# PS3_PMIC.net
KiCad netlist of a schematic drawn in Altium Designer
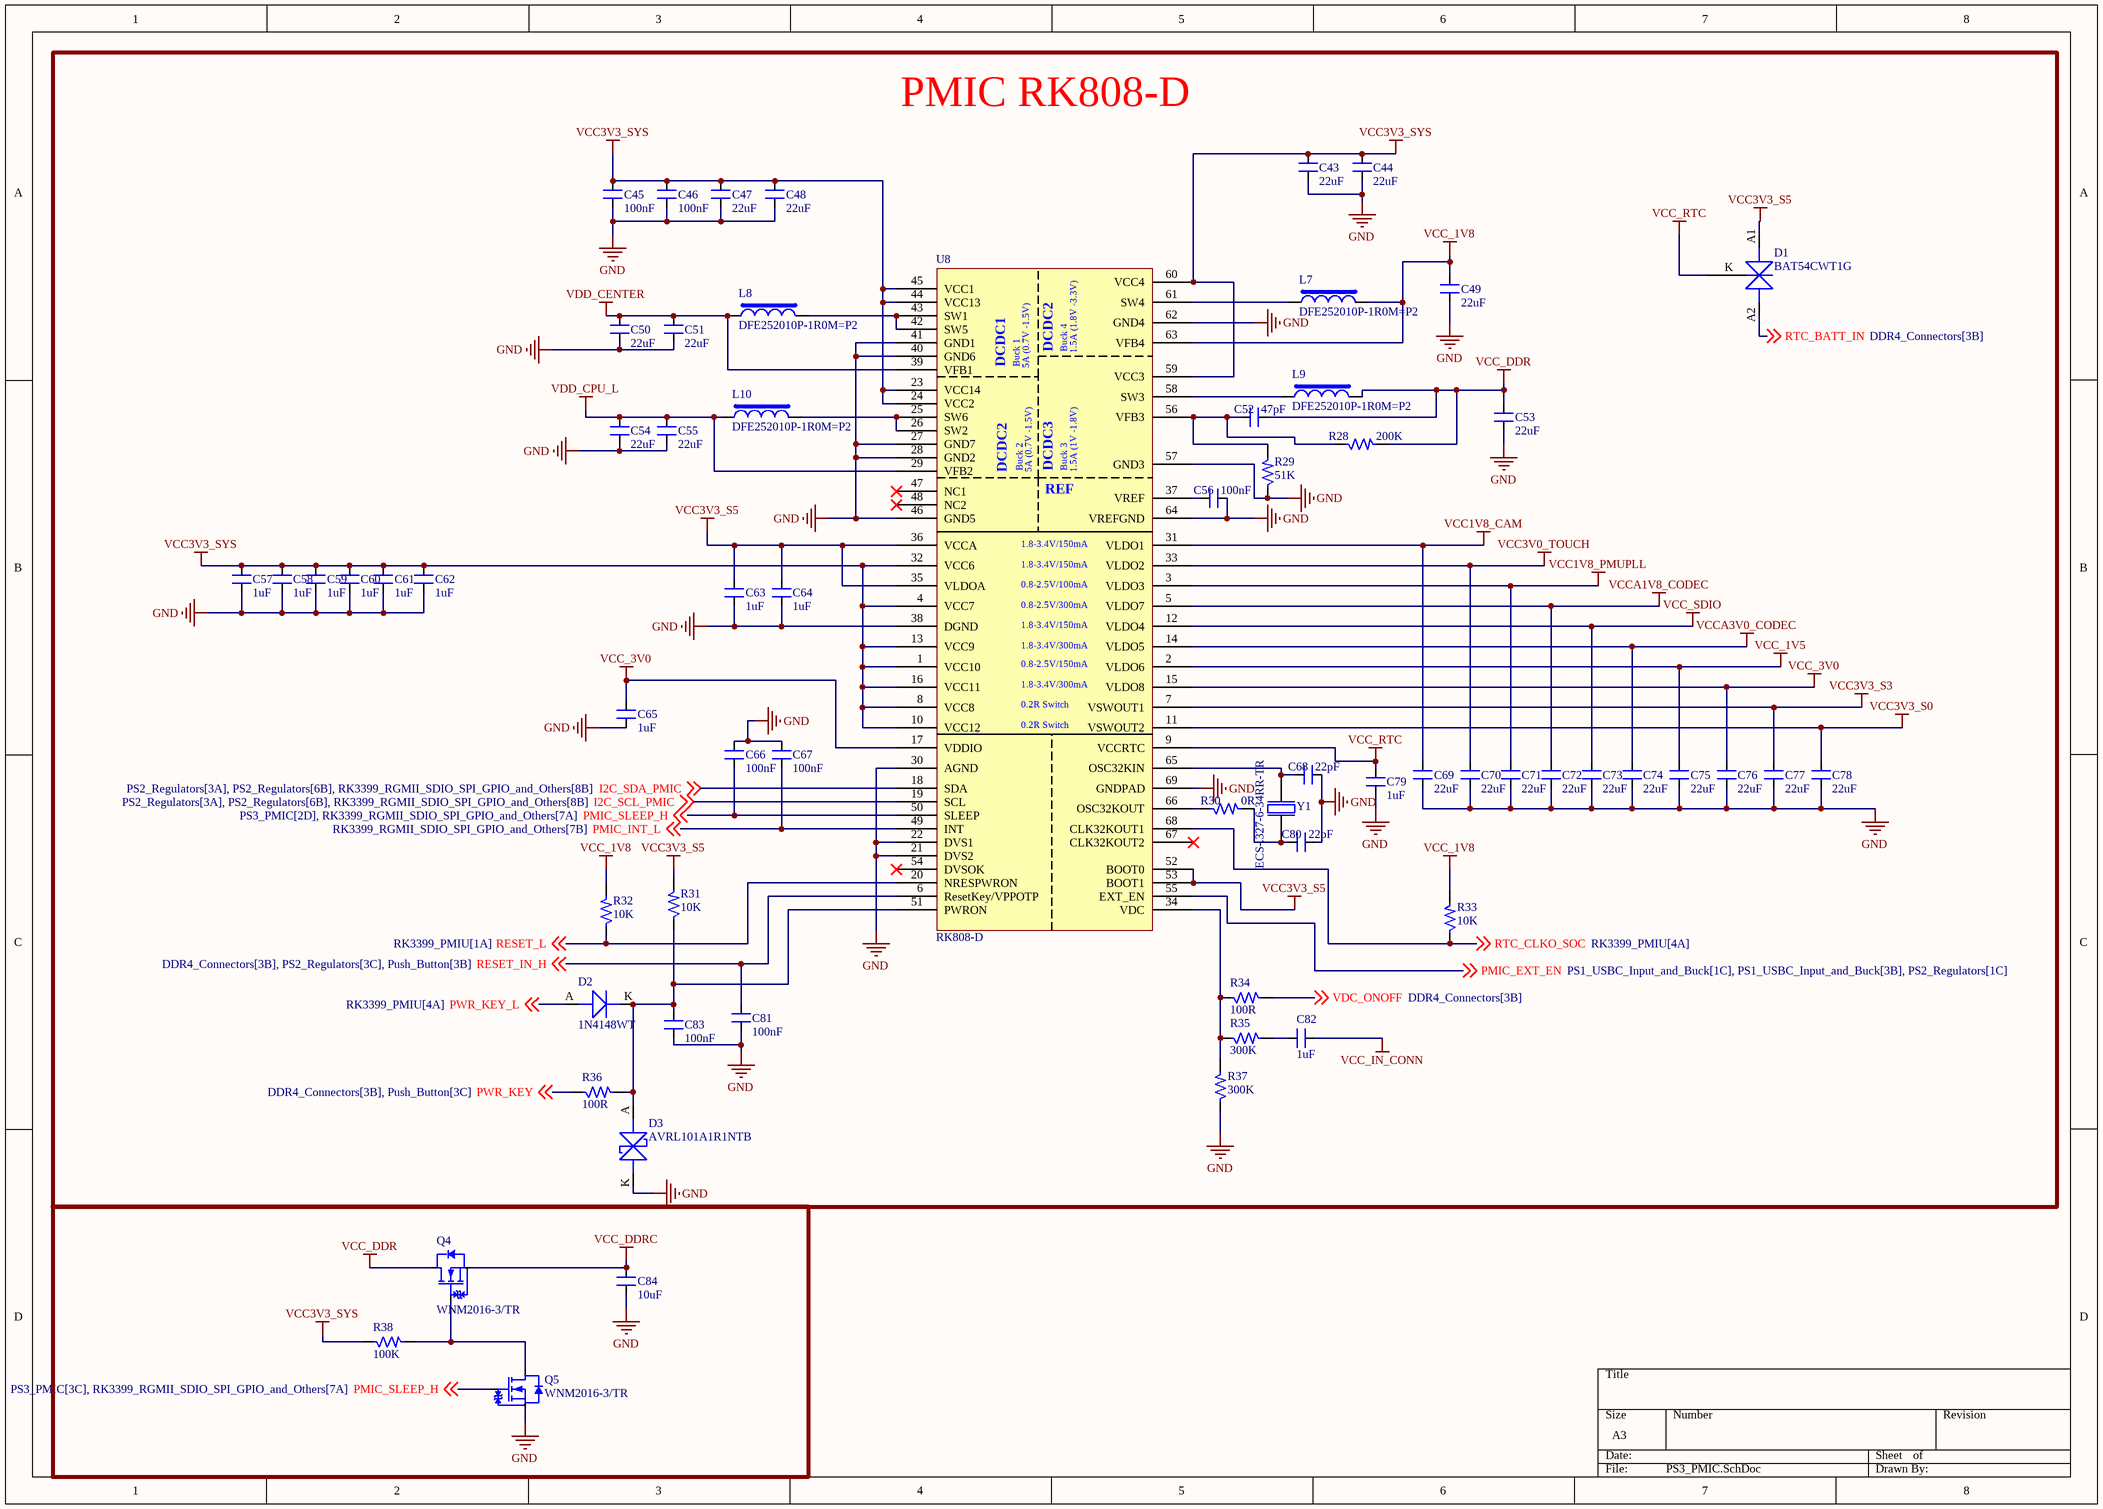
[diagram p0: PS3_PMIC.SchDoc]

(export (version "E")
  (design (tool "Eeschema 10.0.6"))
  (components
    (comp (ref "C43")
      (value "22uF")
      (footprint "CAP_0603")
      (description "22µF ±20% 10V Ceramic Capacitor X5R 0603 (1608 Metric)")
      (fields
        (field (name "MANUFACTURER") "Murata Electronics")
        (field (name "MANUFACTURER PART NUMBER") "GRM188R61A226ME15D")
      )
      (libsource (lib "EsteemPCB_SOM_Course_schlib") (part "CAP_22uF-10V-20%-0603"))
    )
    (comp (ref "C44")
      (value "22uF")
      (footprint "CAP_0603")
      (description "22µF ±20% 10V Ceramic Capacitor X5R 0603 (1608 Metric)")
      (fields
        (field (name "MANUFACTURER") "Murata Electronics")
        (field (name "MANUFACTURER PART NUMBER") "GRM188R61A226ME15D")
      )
      (libsource (lib "EsteemPCB_SOM_Course_schlib") (part "CAP_22uF-10V-20%-0603"))
    )
    (comp (ref "C45")
      (value "100nF")
      (footprint "CAP_0402")
      (description "0.1µF ±10% 25V Ceramic Capacitor X7R 0402 (1005 Metric)")
      (fields
        (field (name "MANUFACTURER") "Walsin Technology Corporation")
        (field (name "MANUFACTURER PART NUMBER") "0402B104K250CT")
      )
      (libsource (lib "EsteemPCB_SOM_Course_schlib") (part "CAP_100nF-25V-10%-0402"))
    )
    (comp (ref "C46")
      (value "100nF")
      (footprint "CAP_0402")
      (description "0.1µF ±10% 25V Ceramic Capacitor X7R 0402 (1005 Metric)")
      (fields
        (field (name "MANUFACTURER") "Walsin Technology Corporation")
        (field (name "MANUFACTURER PART NUMBER") "0402B104K250CT")
      )
      (libsource (lib "EsteemPCB_SOM_Course_schlib") (part "CAP_100nF-25V-10%-0402"))
    )
    (comp (ref "C47")
      (value "22uF")
      (footprint "CAP_0603")
      (description "22µF ±20% 10V Ceramic Capacitor X5R 0603 (1608 Metric)")
      (fields
        (field (name "MANUFACTURER") "Murata Electronics")
        (field (name "MANUFACTURER PART NUMBER") "GRM188R61A226ME15D")
      )
      (libsource (lib "EsteemPCB_SOM_Course_schlib") (part "CAP_22uF-10V-20%-0603"))
    )
    (comp (ref "C48")
      (value "22uF")
      (footprint "CAP_0603")
      (description "22µF ±20% 10V Ceramic Capacitor X5R 0603 (1608 Metric)")
      (fields
        (field (name "MANUFACTURER") "Murata Electronics")
        (field (name "MANUFACTURER PART NUMBER") "GRM188R61A226ME15D")
      )
      (libsource (lib "EsteemPCB_SOM_Course_schlib") (part "CAP_22uF-10V-20%-0603"))
    )
    (comp (ref "C49")
      (value "22uF")
      (footprint "CAP_0603")
      (description "22µF ±20% 10V Ceramic Capacitor X5R 0603 (1608 Metric)")
      (fields
        (field (name "MANUFACTURER") "Murata Electronics")
        (field (name "MANUFACTURER PART NUMBER") "GRM188R61A226ME15D")
      )
      (libsource (lib "EsteemPCB_SOM_Course_schlib") (part "CAP_22uF-10V-20%-0603"))
    )
    (comp (ref "C50")
      (value "22uF")
      (footprint "CAP_0603")
      (description "22µF ±20% 10V Ceramic Capacitor X5R 0603 (1608 Metric)")
      (fields
        (field (name "MANUFACTURER") "Murata Electronics")
        (field (name "MANUFACTURER PART NUMBER") "GRM188R61A226ME15D")
      )
      (libsource (lib "EsteemPCB_SOM_Course_schlib") (part "CAP_22uF-10V-20%-0603"))
    )
    (comp (ref "C51")
      (value "22uF")
      (footprint "CAP_0603")
      (description "22µF ±20% 10V Ceramic Capacitor X5R 0603 (1608 Metric)")
      (fields
        (field (name "MANUFACTURER") "Murata Electronics")
        (field (name "MANUFACTURER PART NUMBER") "GRM188R61A226ME15D")
      )
      (libsource (lib "EsteemPCB_SOM_Course_schlib") (part "CAP_22uF-10V-20%-0603"))
    )
    (comp (ref "C52")
      (value "47pF")
      (footprint "CAP_0402")
      (description "47pF ±10% 10V Ceramic Capacitor C0G, NP0 0402 (1005 Metric)")
      (fields
        (field (name "MANUFACTURER") "KEMET")
        (field (name "MANUFACTURER PART NUMBER") "C0402C470K8GAC7867")
      )
      (libsource (lib "EsteemPCB_SOM_Course_schlib") (part "CAP_47pF-10V-10%-0402"))
    )
    (comp (ref "C53")
      (value "22uF")
      (footprint "CAP_0603")
      (description "22µF ±20% 10V Ceramic Capacitor X5R 0603 (1608 Metric)")
      (fields
        (field (name "MANUFACTURER") "Murata Electronics")
        (field (name "MANUFACTURER PART NUMBER") "GRM188R61A226ME15D")
      )
      (libsource (lib "EsteemPCB_SOM_Course_schlib") (part "CAP_22uF-10V-20%-0603"))
    )
    (comp (ref "C54")
      (value "22uF")
      (footprint "CAP_0603")
      (description "22µF ±20% 10V Ceramic Capacitor X5R 0603 (1608 Metric)")
      (fields
        (field (name "MANUFACTURER") "Murata Electronics")
        (field (name "MANUFACTURER PART NUMBER") "GRM188R61A226ME15D")
      )
      (libsource (lib "EsteemPCB_SOM_Course_schlib") (part "CAP_22uF-10V-20%-0603"))
    )
    (comp (ref "C55")
      (value "22uF")
      (footprint "CAP_0603")
      (description "22µF ±20% 10V Ceramic Capacitor X5R 0603 (1608 Metric)")
      (fields
        (field (name "MANUFACTURER") "Murata Electronics")
        (field (name "MANUFACTURER PART NUMBER") "GRM188R61A226ME15D")
      )
      (libsource (lib "EsteemPCB_SOM_Course_schlib") (part "CAP_22uF-10V-20%-0603"))
    )
    (comp (ref "C56")
      (value "100nF")
      (footprint "CAP_0402")
      (description "0.1µF ±10% 25V Ceramic Capacitor X7R 0402 (1005 Metric)")
      (fields
        (field (name "MANUFACTURER") "Walsin Technology Corporation")
        (field (name "MANUFACTURER PART NUMBER") "0402B104K250CT")
      )
      (libsource (lib "EsteemPCB_SOM_Course_schlib") (part "CAP_100nF-25V-10%-0402"))
    )
    (comp (ref "C57")
      (value "1uF")
      (footprint "CAP_0402")
      (description "1µF ±10% 16V Ceramic Capacitor X5R 0402 (1005 Metric)")
      (fields
        (field (name "MANUFACTURER") "Knowles Novacap")
        (field (name "MANUFACTURER PART NUMBER") "0402BW105K160YT")
      )
      (libsource (lib "EsteemPCB_SOM_Course_schlib") (part "CAP_1uF-16V-10%-0402"))
    )
    (comp (ref "C58")
      (value "1uF")
      (footprint "CAP_0402")
      (description "1µF ±10% 16V Ceramic Capacitor X5R 0402 (1005 Metric)")
      (fields
        (field (name "MANUFACTURER") "Knowles Novacap")
        (field (name "MANUFACTURER PART NUMBER") "0402BW105K160YT")
      )
      (libsource (lib "EsteemPCB_SOM_Course_schlib") (part "CAP_1uF-16V-10%-0402"))
    )
    (comp (ref "C59")
      (value "1uF")
      (footprint "CAP_0402")
      (description "1µF ±10% 16V Ceramic Capacitor X5R 0402 (1005 Metric)")
      (fields
        (field (name "MANUFACTURER") "Knowles Novacap")
        (field (name "MANUFACTURER PART NUMBER") "0402BW105K160YT")
      )
      (libsource (lib "EsteemPCB_SOM_Course_schlib") (part "CAP_1uF-16V-10%-0402"))
    )
    (comp (ref "C60")
      (value "1uF")
      (footprint "CAP_0402")
      (description "1µF ±10% 16V Ceramic Capacitor X5R 0402 (1005 Metric)")
      (fields
        (field (name "MANUFACTURER") "Knowles Novacap")
        (field (name "MANUFACTURER PART NUMBER") "0402BW105K160YT")
      )
      (libsource (lib "EsteemPCB_SOM_Course_schlib") (part "CAP_1uF-16V-10%-0402"))
    )
    (comp (ref "C61")
      (value "1uF")
      (footprint "CAP_0402")
      (description "1µF ±10% 16V Ceramic Capacitor X5R 0402 (1005 Metric)")
      (fields
        (field (name "MANUFACTURER") "Knowles Novacap")
        (field (name "MANUFACTURER PART NUMBER") "0402BW105K160YT")
      )
      (libsource (lib "EsteemPCB_SOM_Course_schlib") (part "CAP_1uF-16V-10%-0402"))
    )
    (comp (ref "C62")
      (value "1uF")
      (footprint "CAP_0402")
      (description "1µF ±10% 16V Ceramic Capacitor X5R 0402 (1005 Metric)")
      (fields
        (field (name "MANUFACTURER") "Knowles Novacap")
        (field (name "MANUFACTURER PART NUMBER") "0402BW105K160YT")
      )
      (libsource (lib "EsteemPCB_SOM_Course_schlib") (part "CAP_1uF-16V-10%-0402"))
    )
    (comp (ref "C63")
      (value "1uF")
      (footprint "CAP_0402")
      (description "1µF ±10% 16V Ceramic Capacitor X5R 0402 (1005 Metric)")
      (fields
        (field (name "MANUFACTURER") "Knowles Novacap")
        (field (name "MANUFACTURER PART NUMBER") "0402BW105K160YT")
      )
      (libsource (lib "EsteemPCB_SOM_Course_schlib") (part "CAP_1uF-16V-10%-0402"))
    )
    (comp (ref "C64")
      (value "1uF")
      (footprint "CAP_0402")
      (description "1µF ±10% 16V Ceramic Capacitor X5R 0402 (1005 Metric)")
      (fields
        (field (name "MANUFACTURER") "Knowles Novacap")
        (field (name "MANUFACTURER PART NUMBER") "0402BW105K160YT")
      )
      (libsource (lib "EsteemPCB_SOM_Course_schlib") (part "CAP_1uF-16V-10%-0402"))
    )
    (comp (ref "C65")
      (value "1uF")
      (footprint "CAP_0402")
      (description "1µF ±10% 16V Ceramic Capacitor X5R 0402 (1005 Metric)")
      (fields
        (field (name "MANUFACTURER") "Knowles Novacap")
        (field (name "MANUFACTURER PART NUMBER") "0402BW105K160YT")
      )
      (libsource (lib "EsteemPCB_SOM_Course_schlib") (part "CAP_1uF-16V-10%-0402"))
    )
    (comp (ref "C66")
      (value "100nF")
      (footprint "CAP_0402")
      (description "0.1µF ±10% 25V Ceramic Capacitor X7R 0402 (1005 Metric)")
      (fields
        (field (name "MANUFACTURER") "Walsin Technology Corporation")
        (field (name "MANUFACTURER PART NUMBER") "0402B104K250CT")
      )
      (libsource (lib "EsteemPCB_SOM_Course_schlib") (part "CAP_100nF-25V-10%-0402"))
    )
    (comp (ref "C67")
      (value "100nF")
      (footprint "CAP_0402")
      (description "0.1µF ±10% 25V Ceramic Capacitor X7R 0402 (1005 Metric)")
      (fields
        (field (name "MANUFACTURER") "Walsin Technology Corporation")
        (field (name "MANUFACTURER PART NUMBER") "0402B104K250CT")
      )
      (libsource (lib "EsteemPCB_SOM_Course_schlib") (part "CAP_100nF-25V-10%-0402"))
    )
    (comp (ref "C68")
      (value "22pF")
      (footprint "CAP_0402")
      (description "22pF ±10% 10V Ceramic Capacitor C0G, NP0 0402 (1005 Metric)")
      (fields
        (field (name "MANUFACTURER") "KEMET")
        (field (name "MANUFACTURER PART NUMBER") "C0402C220K8GACTU")
      )
      (libsource (lib "EsteemPCB_SOM_Course_schlib") (part "CAP_22pF-10V-10%-0402"))
    )
    (comp (ref "C69")
      (value "22uF")
      (footprint "CAP_0603")
      (description "22µF ±20% 10V Ceramic Capacitor X5R 0603 (1608 Metric)")
      (fields
        (field (name "MANUFACTURER") "Murata Electronics")
        (field (name "MANUFACTURER PART NUMBER") "GRM188R61A226ME15D")
      )
      (libsource (lib "EsteemPCB_SOM_Course_schlib") (part "CAP_22uF-10V-20%-0603"))
    )
    (comp (ref "C70")
      (value "22uF")
      (footprint "CAP_0603")
      (description "22µF ±20% 10V Ceramic Capacitor X5R 0603 (1608 Metric)")
      (fields
        (field (name "MANUFACTURER") "Murata Electronics")
        (field (name "MANUFACTURER PART NUMBER") "GRM188R61A226ME15D")
      )
      (libsource (lib "EsteemPCB_SOM_Course_schlib") (part "CAP_22uF-10V-20%-0603"))
    )
    (comp (ref "C71")
      (value "22uF")
      (footprint "CAP_0603")
      (description "22µF ±20% 10V Ceramic Capacitor X5R 0603 (1608 Metric)")
      (fields
        (field (name "MANUFACTURER") "Murata Electronics")
        (field (name "MANUFACTURER PART NUMBER") "GRM188R61A226ME15D")
      )
      (libsource (lib "EsteemPCB_SOM_Course_schlib") (part "CAP_22uF-10V-20%-0603"))
    )
    (comp (ref "C72")
      (value "22uF")
      (footprint "CAP_0603")
      (description "22µF ±20% 10V Ceramic Capacitor X5R 0603 (1608 Metric)")
      (fields
        (field (name "MANUFACTURER") "Murata Electronics")
        (field (name "MANUFACTURER PART NUMBER") "GRM188R61A226ME15D")
      )
      (libsource (lib "EsteemPCB_SOM_Course_schlib") (part "CAP_22uF-10V-20%-0603"))
    )
    (comp (ref "C73")
      (value "22uF")
      (footprint "CAP_0603")
      (description "22µF ±20% 10V Ceramic Capacitor X5R 0603 (1608 Metric)")
      (fields
        (field (name "MANUFACTURER") "Murata Electronics")
        (field (name "MANUFACTURER PART NUMBER") "GRM188R61A226ME15D")
      )
      (libsource (lib "EsteemPCB_SOM_Course_schlib") (part "CAP_22uF-10V-20%-0603"))
    )
    (comp (ref "C74")
      (value "22uF")
      (footprint "CAP_0603")
      (description "22µF ±20% 10V Ceramic Capacitor X5R 0603 (1608 Metric)")
      (fields
        (field (name "MANUFACTURER") "Murata Electronics")
        (field (name "MANUFACTURER PART NUMBER") "GRM188R61A226ME15D")
      )
      (libsource (lib "EsteemPCB_SOM_Course_schlib") (part "CAP_22uF-10V-20%-0603"))
    )
    (comp (ref "C75")
      (value "22uF")
      (footprint "CAP_0603")
      (description "22µF ±20% 10V Ceramic Capacitor X5R 0603 (1608 Metric)")
      (fields
        (field (name "MANUFACTURER") "Murata Electronics")
        (field (name "MANUFACTURER PART NUMBER") "GRM188R61A226ME15D")
      )
      (libsource (lib "EsteemPCB_SOM_Course_schlib") (part "CAP_22uF-10V-20%-0603"))
    )
    (comp (ref "C76")
      (value "22uF")
      (footprint "CAP_0603")
      (description "22µF ±20% 10V Ceramic Capacitor X5R 0603 (1608 Metric)")
      (fields
        (field (name "MANUFACTURER") "Murata Electronics")
        (field (name "MANUFACTURER PART NUMBER") "GRM188R61A226ME15D")
      )
      (libsource (lib "EsteemPCB_SOM_Course_schlib") (part "CAP_22uF-10V-20%-0603"))
    )
    (comp (ref "C77")
      (value "22uF")
      (footprint "CAP_0603")
      (description "22µF ±20% 10V Ceramic Capacitor X5R 0603 (1608 Metric)")
      (fields
        (field (name "MANUFACTURER") "Murata Electronics")
        (field (name "MANUFACTURER PART NUMBER") "GRM188R61A226ME15D")
      )
      (libsource (lib "EsteemPCB_SOM_Course_schlib") (part "CAP_22uF-10V-20%-0603"))
    )
    (comp (ref "C78")
      (value "22uF")
      (footprint "CAP_0603")
      (description "22µF ±20% 10V Ceramic Capacitor X5R 0603 (1608 Metric)")
      (fields
        (field (name "MANUFACTURER") "Murata Electronics")
        (field (name "MANUFACTURER PART NUMBER") "GRM188R61A226ME15D")
      )
      (libsource (lib "EsteemPCB_SOM_Course_schlib") (part "CAP_22uF-10V-20%-0603"))
    )
    (comp (ref "C79")
      (value "1uF")
      (footprint "CAP_0402")
      (description "1µF ±10% 16V Ceramic Capacitor X5R 0402 (1005 Metric)")
      (fields
        (field (name "MANUFACTURER") "Knowles Novacap")
        (field (name "MANUFACTURER PART NUMBER") "0402BW105K160YT")
      )
      (libsource (lib "EsteemPCB_SOM_Course_schlib") (part "CAP_1uF-16V-10%-0402"))
    )
    (comp (ref "C80")
      (value "22pF")
      (footprint "CAP_0402")
      (description "22pF ±10% 10V Ceramic Capacitor C0G, NP0 0402 (1005 Metric)")
      (fields
        (field (name "MANUFACTURER") "KEMET")
        (field (name "MANUFACTURER PART NUMBER") "C0402C220K8GACTU")
      )
      (libsource (lib "EsteemPCB_SOM_Course_schlib") (part "CAP_22pF-10V-10%-0402"))
    )
    (comp (ref "C81")
      (value "100nF")
      (footprint "CAP_0402")
      (description "0.1µF ±10% 25V Ceramic Capacitor X7R 0402 (1005 Metric)")
      (fields
        (field (name "MANUFACTURER") "Walsin Technology Corporation")
        (field (name "MANUFACTURER PART NUMBER") "0402B104K250CT")
      )
      (libsource (lib "EsteemPCB_SOM_Course_schlib") (part "CAP_100nF-25V-10%-0402"))
    )
    (comp (ref "C82")
      (value "1uF")
      (footprint "CAP_0402")
      (description "1µF ±10% 16V Ceramic Capacitor X5R 0402 (1005 Metric)")
      (fields
        (field (name "MANUFACTURER") "Knowles Novacap")
        (field (name "MANUFACTURER PART NUMBER") "0402BW105K160YT")
      )
      (libsource (lib "EsteemPCB_SOM_Course_schlib") (part "CAP_1uF-16V-10%-0402"))
    )
    (comp (ref "C83")
      (value "100nF")
      (footprint "CAP_0402")
      (description "0.1µF ±10% 25V Ceramic Capacitor X7R 0402 (1005 Metric)")
      (fields
        (field (name "MANUFACTURER") "Walsin Technology Corporation")
        (field (name "MANUFACTURER PART NUMBER") "0402B104K250CT")
      )
      (libsource (lib "EsteemPCB_SOM_Course_schlib") (part "CAP_100nF-25V-10%-0402"))
    )
    (comp (ref "C84")
      (value "10uF")
      (footprint "CAP_0402")
      (description "10µF ±20% 10V Ceramic Capacitor X5R 0402 (1005 Metric)")
      (fields
        (field (name "MANUFACTURER PART NUMBER") "CL05A106MP5NUNC")
        (field (name "MANUFACTURER") "Samsung Electro-Mechanics")
      )
      (libsource (lib "EsteemPCB_SOM_Course_schlib") (part "CAP_10uF-10V-20%-0402"))
    )
    (comp (ref "D1")
      (value "BAT54CWT1G")
      (footprint "DIO_SOT-323-3")
      (description "Diode Array 1 Pair Common Cathode Schottky 30V 200mA (DC) Surface Mount SC-70, SOT-323")
      (fields (field (name "MANUFACTURER") "ON Semiconductor"))
      (libsource (lib "EsteemPCB_SOM_Course_schlib") (part "DIO-S-A_30V-200mA-SOT-323"))
    )
    (comp (ref "D2")
      (value "1N4148WT")
      (footprint "DIO_SOD523")
      (description "Diode Standard 100V 300mA (DC) Surface Mount SOD-123")
      (fields (field (name "MANUFACTURER") "FAIRCHILD"))
      (libsource (lib "EsteemPCB_SOM_Course_schlib") (part "DIO_75V-200mA-SOD-523F"))
    )
    (comp (ref "D3")
      (value "AVRL101A1R1NTB")
      (footprint "DIO_0402_SMD")
      (description "39V Varistor 1 Circuit Surface Mount, MLCV 0402 (1005 Metric)")
      (fields (field (name "MANUFACTURER") "TDK Corporation"))
      (libsource (lib "EsteemPCB_SOM_Course_schlib") (part "DIO-T_10V-39V-0402"))
    )
    (comp (ref "L7")
      (value "DFE252010P-1R0M=P2")
      (footprint "IND_1008")
      (description "1µH Shielded Wirewound Inductor 3.8A 54mOhm Max 1008 (2520 Metric)")
      (fields (field (name "MANUFACTURER") "Murata Electronics"))
      (libsource (lib "EsteemPCB_SOM_Course_schlib") (part "IND_1uH-3.8A-20%-1008"))
    )
    (comp (ref "L8")
      (value "DFE252010P-1R0M=P2")
      (footprint "IND_1008")
      (description "1µH Shielded Wirewound Inductor 3.8A 54mOhm Max 1008 (2520 Metric)")
      (fields (field (name "MANUFACTURER") "Murata Electronics"))
      (libsource (lib "EsteemPCB_SOM_Course_schlib") (part "IND_1uH-3.8A-20%-1008"))
    )
    (comp (ref "L9")
      (value "DFE252010P-1R0M=P2")
      (footprint "IND_1008")
      (description "1µH Shielded Wirewound Inductor 3.8A 54mOhm Max 1008 (2520 Metric)")
      (fields (field (name "MANUFACTURER") "Murata Electronics"))
      (libsource (lib "EsteemPCB_SOM_Course_schlib") (part "IND_1uH-3.8A-20%-1008"))
    )
    (comp (ref "L10")
      (value "DFE252010P-1R0M=P2")
      (footprint "IND_1008")
      (description "1µH Shielded Wirewound Inductor 3.8A 54mOhm Max 1008 (2520 Metric)")
      (fields (field (name "MANUFACTURER") "Murata Electronics"))
      (libsource (lib "EsteemPCB_SOM_Course_schlib") (part "IND_1uH-3.8A-20%-1008"))
    )
    (comp (ref "Q4")
      (value "WNM2016-3/TR")
      (footprint "SOT 23-3")
      (description "N Channel 20V 2.9A 1V @ 250uA 47mΩ @ 3.6A,4.5V 700mW SOT-23(SOT-23-3) MOSFET RoHS")
      (fields (field (name "MANUFACTURER") "WILLSEMI(Will Semicon)"))
      (libsource (lib "EsteemPCB_SOM_Course_schlib") (part "MOSFET-N_20V-2.9A-SOT-23"))
    )
    (comp (ref "Q5")
      (value "WNM2016-3/TR")
      (footprint "SOT 23-3")
      (description "N Channel 20V 2.9A 1V @ 250uA 47mΩ @ 3.6A,4.5V 700mW SOT-23(SOT-23-3) MOSFET RoHS")
      (fields (field (name "MANUFACTURER") "WILLSEMI(Will Semicon)"))
      (libsource (lib "EsteemPCB_SOM_Course_schlib") (part "MOSFET-N_20V-2.9A-SOT-23"))
    )
    (comp (ref "R28")
      (value "200K")
      (footprint "RES_0402")
      (description "200 kOhms ±1% 0.1W, 1/10W Chip Resistor 0402 (1005 Metric) Automotive AEC-Q200 Thick Film")
      (fields
        (field (name "MANUFACTURER") "Panasonic Electronic Components")
        (field (name "MANUFACTURER PART NUMBER") "ERJ-2RKF2003X")
      )
      (libsource (lib "EsteemPCB_SOM_Course_schlib") (part "RES_200K-0.1W-1%-0402"))
    )
    (comp (ref "R29")
      (value "51K")
      (footprint "RES_0402")
      (description "51 kOhms ±1% 0.1W, 1/10W Chip Resistor 0402 (1005 Metric) Automotive AEC-Q200 Thick Film")
      (fields
        (field (name "MANUFACTURER") "Panasonic Electronic Components")
        (field (name "MANUFACTURER PART NUMBER") "ERJ-2RKF5102X")
      )
      (libsource (lib "EsteemPCB_SOM_Course_schlib") (part "RES_51K-0.1W-1%-0402"))
    )
    (comp (ref "R30")
      (value "0R")
      (footprint "RES_0402")
      (description "0 Ohms Jumper 0.1W, 1/10W Chip Resistor 0402 (1005 Metric) Automotive AEC-Q200 Thick Film")
      (fields
        (field (name "MANUFACTURER") "Panasonic Electronic Components")
        (field (name "MANUFACTURER PART NUMBER") "ERJ-2GE0R00X")
      )
      (libsource (lib "EsteemPCB_SOM_Course_schlib") (part "RES_0R-0.1W-1%-0402"))
    )
    (comp (ref "R31")
      (value "10K")
      (footprint "RES_0402")
      (description "10 kOhms ±1% 0.1W, 1/10W Chip Resistor 0402 (1005 Metric) Anti-Sulfur Thin Film")
      (fields
        (field (name "MANUFACTURER") "Vishay Beyschlag/Draloric/BC Components")
        (field (name "MANUFACTURER PART NUMBER") "MCS04020C1002FE000")
      )
      (libsource (lib "EsteemPCB_SOM_Course_schlib") (part "RES_10K-0.1W-1%-0402"))
    )
    (comp (ref "R32")
      (value "10K")
      (footprint "RES_0402")
      (description "10 kOhms ±1% 0.1W, 1/10W Chip Resistor 0402 (1005 Metric) Anti-Sulfur Thin Film")
      (fields
        (field (name "MANUFACTURER") "Vishay Beyschlag/Draloric/BC Components")
        (field (name "MANUFACTURER PART NUMBER") "MCS04020C1002FE000")
      )
      (libsource (lib "EsteemPCB_SOM_Course_schlib") (part "RES_10K-0.1W-1%-0402"))
    )
    (comp (ref "R33")
      (value "10K")
      (footprint "RES_0402")
      (description "10 kOhms ±1% 0.1W, 1/10W Chip Resistor 0402 (1005 Metric) Anti-Sulfur Thin Film")
      (fields
        (field (name "MANUFACTURER") "Vishay Beyschlag/Draloric/BC Components")
        (field (name "MANUFACTURER PART NUMBER") "MCS04020C1002FE000")
      )
      (libsource (lib "EsteemPCB_SOM_Course_schlib") (part "RES_10K-0.1W-1%-0402"))
    )
    (comp (ref "R34")
      (value "100R")
      (footprint "RES_0402")
      (fields
        (field (name "MANUFACTURER") "KOA Speer Electronics, Inc.")
        (field (name "MANUFACTURER PART NUMBER") "RK73H1ETTP1000F")
      )
      (libsource (lib "EsteemPCB_SOM_Course_schlib") (part "RES_100R-0.1W-1%-0402"))
    )
    (comp (ref "R35")
      (value "300K")
      (footprint "RES_0402")
      (description "300 kOhms ±1% 0.1W, 1/10W Chip Resistor 0402 (1005 Metric) Automotive AEC-Q200 Thick Film")
      (fields
        (field (name "MANUFACTURER") "Panasonic Electronic Components")
        (field (name "MANUFACTURER PART NUMBER") "ERJ-2RKF3003X")
      )
      (libsource (lib "EsteemPCB_SOM_Course_schlib") (part "RES_300K-0.1W-1%-0402"))
    )
    (comp (ref "R36")
      (value "100R")
      (footprint "RES_0402")
      (fields
        (field (name "MANUFACTURER") "KOA Speer Electronics, Inc.")
        (field (name "MANUFACTURER PART NUMBER") "RK73H1ETTP1000F")
      )
      (libsource (lib "EsteemPCB_SOM_Course_schlib") (part "RES_100R-0.1W-1%-0402"))
    )
    (comp (ref "R37")
      (value "300K")
      (footprint "RES_0402")
      (description "300 kOhms ±1% 0.1W, 1/10W Chip Resistor 0402 (1005 Metric) Automotive AEC-Q200 Thick Film")
      (fields
        (field (name "MANUFACTURER") "Panasonic Electronic Components")
        (field (name "MANUFACTURER PART NUMBER") "ERJ-2RKF3003X")
      )
      (libsource (lib "EsteemPCB_SOM_Course_schlib") (part "RES_300K-0.1W-1%-0402"))
    )
    (comp (ref "R38")
      (value "100K")
      (footprint "RES_0402")
      (description "100 kOhms ±1% 0.1W, 1/10W Chip Resistor 0402 (1005 Metric) Anti-Sulfur Thin Film")
      (fields
        (field (name "MANUFACTURER") "Vishay Beyschlag/Draloric/BC Components")
        (field (name "MANUFACTURER PART NUMBER") "MCS04020C1003FE000")
      )
      (libsource (lib "EsteemPCB_SOM_Course_schlib") (part "RES_100K-0.1W-1%-0402"))
    )
    (comp (ref "U8")
      (value "RK808-D")
      (footprint "QFN68_13.7_220.4X220.4_SMD")
      (description "The RK808 is a complete power supply solution for Portable systems.")
      (fields (field (name "MANUFACTURER") "Rockchip"))
      (libsource (lib "EsteemPCB_SOM_Course_schlib") (part "IC_RK808-D-QFN68"))
    )
    (comp (ref "Y1")
      (value "ECS-.327-6-34RR-TR")
      (footprint "XTAL_ECS-.327-6-34RR-TR")
      (description "32.768kHz ±20ppm Crystal 12pF 80 kOhms 2-SMD, No Lead")
      (fields (field (name "MANUFACTURER") "Ecliptek"))
      (libsource (lib "EsteemPCB_SOM_Course_schlib") (part "XTAL_32.768Khz-22pF-SMD"))
    )
  )
  (nets
    (net (code "1") (name "GND") (class "Default")
      (node (ref "C43") (pin "1") (pinfunction "1_1") (pintype "passive"))
      (node (ref "C44") (pin "1") (pinfunction "1_1") (pintype "passive"))
      (node (ref "C45") (pin "1") (pinfunction "1_1") (pintype "passive"))
      (node (ref "C46") (pin "1") (pinfunction "1_1") (pintype "passive"))
      (node (ref "C47") (pin "1") (pinfunction "1_1") (pintype "passive"))
      (node (ref "C48") (pin "1") (pinfunction "1_1") (pintype "passive"))
      (node (ref "C49") (pin "1") (pinfunction "1_1") (pintype "passive"))
      (node (ref "C50") (pin "1") (pinfunction "1_1") (pintype "passive"))
      (node (ref "C51") (pin "1") (pinfunction "1_1") (pintype "passive"))
      (node (ref "C53") (pin "1") (pinfunction "1_1") (pintype "passive"))
      (node (ref "C54") (pin "1") (pinfunction "1_1") (pintype "passive"))
      (node (ref "C55") (pin "1") (pinfunction "1_1") (pintype "passive"))
      (node (ref "C56") (pin "2") (pinfunction "2_2") (pintype "passive"))
      (node (ref "C57") (pin "1") (pinfunction "1_1") (pintype "passive"))
      (node (ref "C58") (pin "1") (pinfunction "1_1") (pintype "passive"))
      (node (ref "C59") (pin "1") (pinfunction "1_1") (pintype "passive"))
      (node (ref "C60") (pin "1") (pinfunction "1_1") (pintype "passive"))
      (node (ref "C61") (pin "1") (pinfunction "1_1") (pintype "passive"))
      (node (ref "C62") (pin "1") (pinfunction "1_1") (pintype "passive"))
      (node (ref "C63") (pin "1") (pinfunction "1_1") (pintype "passive"))
      (node (ref "C64") (pin "1") (pinfunction "1_1") (pintype "passive"))
      (node (ref "C65") (pin "1") (pinfunction "1_1") (pintype "passive"))
      (node (ref "C66") (pin "2") (pinfunction "2_2") (pintype "passive"))
      (node (ref "C67") (pin "2") (pinfunction "2_2") (pintype "passive"))
      (node (ref "C68") (pin "2") (pinfunction "2_2") (pintype "passive"))
      (node (ref "C69") (pin "1") (pinfunction "1_1") (pintype "passive"))
      (node (ref "C70") (pin "1") (pinfunction "1_1") (pintype "passive"))
      (node (ref "C71") (pin "1") (pinfunction "1_1") (pintype "passive"))
      (node (ref "C72") (pin "1") (pinfunction "1_1") (pintype "passive"))
      (node (ref "C73") (pin "1") (pinfunction "1_1") (pintype "passive"))
      (node (ref "C74") (pin "1") (pinfunction "1_1") (pintype "passive"))
      (node (ref "C75") (pin "1") (pinfunction "1_1") (pintype "passive"))
      (node (ref "C76") (pin "1") (pinfunction "1_1") (pintype "passive"))
      (node (ref "C77") (pin "1") (pinfunction "1_1") (pintype "passive"))
      (node (ref "C78") (pin "1") (pinfunction "1_1") (pintype "passive"))
      (node (ref "C79") (pin "1") (pinfunction "1_1") (pintype "passive"))
      (node (ref "C80") (pin "2") (pinfunction "2_2") (pintype "passive"))
      (node (ref "C81") (pin "1") (pinfunction "1_1") (pintype "passive"))
      (node (ref "C83") (pin "1") (pinfunction "1_1") (pintype "passive"))
      (node (ref "C84") (pin "1") (pinfunction "1_1") (pintype "passive"))
      (node (ref "D3") (pin "K") (pinfunction "K_K") (pintype "passive"))
      (node (ref "Q5") (pin "2") (pinfunction "S_2") (pintype "passive"))
      (node (ref "R29") (pin "1") (pinfunction "1_1") (pintype "passive"))
      (node (ref "R37") (pin "1") (pinfunction "1_1") (pintype "passive"))
      (node (ref "U8") (pin "21") (pinfunction "DVS2_21") (pintype "passive"))
      (node (ref "U8") (pin "22") (pinfunction "DVS1_22") (pintype "passive"))
      (node (ref "U8") (pin "27") (pinfunction "GND7_27") (pintype "passive"))
      (node (ref "U8") (pin "28") (pinfunction "GND2_28") (pintype "passive"))
      (node (ref "U8") (pin "30") (pinfunction "AGND_30") (pintype "passive"))
      (node (ref "U8") (pin "38") (pinfunction "DGND_38") (pintype "passive"))
      (node (ref "U8") (pin "40") (pinfunction "GND6_40") (pintype "passive"))
      (node (ref "U8") (pin "41") (pinfunction "GND1_41") (pintype "passive"))
      (node (ref "U8") (pin "46") (pinfunction "GND5_46") (pintype "passive"))
      (node (ref "U8") (pin "57") (pinfunction "GND3_57") (pintype "passive"))
      (node (ref "U8") (pin "62") (pinfunction "GND4_62") (pintype "passive"))
      (node (ref "U8") (pin "64") (pinfunction "VREFGND_64") (pintype "passive"))
      (node (ref "U8") (pin "69") (pinfunction "GNDPAD_69") (pintype "passive"))
    )
    (net (code "2") (name "I2C_SCL_PMIC") (class "Default")
      (node (ref "U8") (pin "19") (pinfunction "SCL_19") (pintype "passive"))
    )
    (net (code "3") (name "I2C_SDA_PMIC") (class "Default")
      (node (ref "U8") (pin "18") (pinfunction "SDA_18") (pintype "passive"))
    )
    (net (code "4") (name "Net-(C80-Pad1)") (class "Default")
      (node (ref "C80") (pin "1") (pinfunction "1_1") (pintype "passive"))
      (node (ref "R30") (pin "2") (pinfunction "2_2") (pintype "passive"))
      (node (ref "Y1") (pin "1") (pinfunction "1_1") (pintype "passive"))
    )
    (net (code "5") (name "Net-(C82-Pad1)") (class "Default")
      (node (ref "C82") (pin "1") (pinfunction "1_1") (pintype "passive"))
      (node (ref "R35") (pin "2") (pinfunction "2_2") (pintype "passive"))
    )
    (net (code "6") (name "Net-(D2-CATHODE)") (class "Default")
      (node (ref "C83") (pin "2") (pinfunction "2_2") (pintype "passive"))
      (node (ref "D2") (pin "K") (pinfunction "CATHODE_K") (pintype "passive"))
      (node (ref "D3") (pin "A") (pinfunction "A_A") (pintype "passive"))
      (node (ref "R31") (pin "1") (pinfunction "1_1") (pintype "passive"))
      (node (ref "R36") (pin "2") (pinfunction "2_2") (pintype "passive"))
      (node (ref "U8") (pin "51") (pinfunction "PWRON_51") (pintype "passive"))
    )
    (net (code "7") (name "Net-(Q4-G)") (class "Default")
      (node (ref "Q4") (pin "1") (pinfunction "G_1") (pintype "passive"))
      (node (ref "Q5") (pin "3") (pinfunction "D_3") (pintype "passive"))
      (node (ref "R38") (pin "2") (pinfunction "2_2") (pintype "passive"))
    )
    (net (code "8") (name "Net-(U8-OSC32KIN)") (class "Default")
      (node (ref "C68") (pin "1") (pinfunction "1_1") (pintype "passive"))
      (node (ref "U8") (pin "65") (pinfunction "OSC32KIN_65") (pintype "passive"))
      (node (ref "Y1") (pin "2") (pinfunction "2_2") (pintype "passive"))
    )
    (net (code "9") (name "Net-(U8-OSC32KOUT)") (class "Default")
      (node (ref "R30") (pin "1") (pinfunction "1_1") (pintype "passive"))
      (node (ref "U8") (pin "66") (pinfunction "OSC32KOUT_66") (pintype "passive"))
    )
    (net (code "10") (name "Net-(U8-SW1)") (class "Default")
      (node (ref "L8") (pin "2") (pinfunction "2_2") (pintype "passive"))
      (node (ref "U8") (pin "42") (pinfunction "SW5_42") (pintype "passive"))
      (node (ref "U8") (pin "43") (pinfunction "SW1_43") (pintype "passive"))
    )
    (net (code "11") (name "Net-(U8-SW2)") (class "Default")
      (node (ref "L10") (pin "2") (pinfunction "2_2") (pintype "passive"))
      (node (ref "U8") (pin "25") (pinfunction "SW6_25") (pintype "passive"))
      (node (ref "U8") (pin "26") (pinfunction "SW2_26") (pintype "passive"))
    )
    (net (code "12") (name "Net-(U8-SW3)") (class "Default")
      (node (ref "L9") (pin "1") (pinfunction "1_1") (pintype "passive"))
      (node (ref "U8") (pin "58") (pinfunction "SW3_58") (pintype "passive"))
    )
    (net (code "13") (name "Net-(U8-SW4)") (class "Default")
      (node (ref "L7") (pin "1") (pinfunction "1_1") (pintype "passive"))
      (node (ref "U8") (pin "61") (pinfunction "SW4_61") (pintype "passive"))
    )
    (net (code "14") (name "Net-(U8-VDC)") (class "Default")
      (node (ref "R34") (pin "1") (pinfunction "1_1") (pintype "passive"))
      (node (ref "R35") (pin "1") (pinfunction "1_1") (pintype "passive"))
      (node (ref "R37") (pin "2") (pinfunction "2_2") (pintype "passive"))
      (node (ref "U8") (pin "34") (pinfunction "VDC_34") (pintype "passive"))
    )
    (net (code "15") (name "Net-(U8-VFB3)") (class "Default")
      (node (ref "C52") (pin "1") (pinfunction "1_1") (pintype "passive"))
      (node (ref "R28") (pin "1") (pinfunction "1_1") (pintype "passive"))
      (node (ref "R29") (pin "2") (pinfunction "2_2") (pintype "passive"))
      (node (ref "U8") (pin "56") (pinfunction "VFB3_56") (pintype "passive"))
    )
    (net (code "16") (name "Net-(U8-VREF)") (class "Default")
      (node (ref "C56") (pin "1") (pinfunction "1_1") (pintype "passive"))
      (node (ref "U8") (pin "37") (pinfunction "VREF_37") (pintype "passive"))
    )
    (net (code "17") (name "PMIC_EXT_EN") (class "Default")
      (node (ref "U8") (pin "55") (pinfunction "EXT_EN_55") (pintype "passive"))
    )
    (net (code "18") (name "PMIC_INT_L") (class "Default")
      (node (ref "C67") (pin "1") (pinfunction "1_1") (pintype "passive"))
      (node (ref "U8") (pin "49") (pinfunction "INT_49") (pintype "passive"))
    )
    (net (code "19") (name "PMIC_SLEEP_H") (class "Default")
      (node (ref "C66") (pin "1") (pinfunction "1_1") (pintype "passive"))
      (node (ref "Q5") (pin "1") (pinfunction "G_1") (pintype "passive"))
      (node (ref "U8") (pin "50") (pinfunction "SLEEP_50") (pintype "passive"))
    )
    (net (code "20") (name "PWR_KEY") (class "Default")
      (node (ref "R36") (pin "1") (pinfunction "1_1") (pintype "passive"))
    )
    (net (code "21") (name "PWR_KEY_L") (class "Default")
      (node (ref "D2") (pin "A") (pinfunction "ANODE_A") (pintype "passive"))
    )
    (net (code "22") (name "RESET_IN_H") (class "Default")
      (node (ref "C81") (pin "2") (pinfunction "2_2") (pintype "passive"))
      (node (ref "U8") (pin "6") (pinfunction "ResetKey/VPPOTP_6") (pintype "passive"))
    )
    (net (code "23") (name "RESET_L") (class "Default")
      (node (ref "R32") (pin "1") (pinfunction "1_1") (pintype "passive"))
      (node (ref "U8") (pin "20") (pinfunction "NRESPWRON_20") (pintype "passive"))
    )
    (net (code "24") (name "RTC_BATT_IN") (class "Default")
      (node (ref "D1") (pin "A2") (pinfunction "A2_A2") (pintype "passive"))
    )
    (net (code "25") (name "RTC_CLKO_SOC") (class "Default")
      (node (ref "R33") (pin "1") (pinfunction "1_1") (pintype "passive"))
      (node (ref "U8") (pin "68") (pinfunction "CLK32KOUT1_68") (pintype "passive"))
    )
    (net (code "26") (name "VCC1V8_CAM") (class "Default")
      (node (ref "C69") (pin "2") (pinfunction "2_2") (pintype "passive"))
      (node (ref "U8") (pin "31") (pinfunction "VLDO1_31") (pintype "passive"))
    )
    (net (code "27") (name "VCC1V8_PMUPLL") (class "Default")
      (node (ref "C71") (pin "2") (pinfunction "2_2") (pintype "passive"))
      (node (ref "U8") (pin "3") (pinfunction "VLDO3_3") (pintype "passive"))
    )
    (net (code "28") (name "VCC3V0_TOUCH") (class "Default")
      (node (ref "C70") (pin "2") (pinfunction "2_2") (pintype "passive"))
      (node (ref "U8") (pin "33") (pinfunction "VLDO2_33") (pintype "passive"))
    )
    (net (code "29") (name "VCC3V3_S0") (class "Default")
      (node (ref "C78") (pin "2") (pinfunction "2_2") (pintype "passive"))
      (node (ref "U8") (pin "11") (pinfunction "VSWOUT2_11") (pintype "passive"))
    )
    (net (code "30") (name "VCC3V3_S3") (class "Default")
      (node (ref "C77") (pin "2") (pinfunction "2_2") (pintype "passive"))
      (node (ref "U8") (pin "7") (pinfunction "VSWOUT1_7") (pintype "passive"))
    )
    (net (code "31") (name "VCC3V3_S5") (class "Default")
      (node (ref "C63") (pin "2") (pinfunction "2_2") (pintype "passive"))
      (node (ref "C64") (pin "2") (pinfunction "2_2") (pintype "passive"))
      (node (ref "D1") (pin "A1") (pinfunction "A1_A1") (pintype "passive"))
      (node (ref "R31") (pin "2") (pinfunction "2_2") (pintype "passive"))
      (node (ref "U8") (pin "35") (pinfunction "VLDOA_35") (pintype "passive"))
      (node (ref "U8") (pin "36") (pinfunction "VCCA_36") (pintype "passive"))
      (node (ref "U8") (pin "52") (pinfunction "BOOT0_52") (pintype "passive"))
      (node (ref "U8") (pin "53") (pinfunction "BOOT1_53") (pintype "passive"))
    )
    (net (code "32") (name "VCC3V3_SYS") (class "Default")
      (node (ref "C43") (pin "2") (pinfunction "2_2") (pintype "passive"))
      (node (ref "C44") (pin "2") (pinfunction "2_2") (pintype "passive"))
      (node (ref "C45") (pin "2") (pinfunction "2_2") (pintype "passive"))
      (node (ref "C46") (pin "2") (pinfunction "2_2") (pintype "passive"))
      (node (ref "C47") (pin "2") (pinfunction "2_2") (pintype "passive"))
      (node (ref "C48") (pin "2") (pinfunction "2_2") (pintype "passive"))
      (node (ref "C57") (pin "2") (pinfunction "2_2") (pintype "passive"))
      (node (ref "C58") (pin "2") (pinfunction "2_2") (pintype "passive"))
      (node (ref "C59") (pin "2") (pinfunction "2_2") (pintype "passive"))
      (node (ref "C60") (pin "2") (pinfunction "2_2") (pintype "passive"))
      (node (ref "C61") (pin "2") (pinfunction "2_2") (pintype "passive"))
      (node (ref "C62") (pin "2") (pinfunction "2_2") (pintype "passive"))
      (node (ref "R38") (pin "1") (pinfunction "1_1") (pintype "passive"))
      (node (ref "U8") (pin "1") (pinfunction "VCC10_1") (pintype "passive"))
      (node (ref "U8") (pin "10") (pinfunction "VCC12_10") (pintype "passive"))
      (node (ref "U8") (pin "13") (pinfunction "VCC9_13") (pintype "passive"))
      (node (ref "U8") (pin "16") (pinfunction "VCC11_16") (pintype "passive"))
      (node (ref "U8") (pin "23") (pinfunction "VCC14_23") (pintype "passive"))
      (node (ref "U8") (pin "24") (pinfunction "VCC2_24") (pintype "passive"))
      (node (ref "U8") (pin "32") (pinfunction "VCC6_32") (pintype "passive"))
      (node (ref "U8") (pin "4") (pinfunction "VCC7_4") (pintype "passive"))
      (node (ref "U8") (pin "44") (pinfunction "VCC13_44") (pintype "passive"))
      (node (ref "U8") (pin "45") (pinfunction "VCC1_45") (pintype "passive"))
      (node (ref "U8") (pin "59") (pinfunction "VCC3_59") (pintype "passive"))
      (node (ref "U8") (pin "60") (pinfunction "VCC4_60") (pintype "passive"))
      (node (ref "U8") (pin "8") (pinfunction "VCC8_8") (pintype "passive"))
    )
    (net (code "33") (name "VCCA1V8_CODEC") (class "Default")
      (node (ref "C72") (pin "2") (pinfunction "2_2") (pintype "passive"))
      (node (ref "U8") (pin "5") (pinfunction "VLDO7_5") (pintype "passive"))
    )
    (net (code "34") (name "VCCA3V0_CODEC") (class "Default")
      (node (ref "C74") (pin "2") (pinfunction "2_2") (pintype "passive"))
      (node (ref "U8") (pin "14") (pinfunction "VLDO5_14") (pintype "passive"))
    )
    (net (code "35") (name "VCC_1V5") (class "Default")
      (node (ref "C75") (pin "2") (pinfunction "2_2") (pintype "passive"))
      (node (ref "U8") (pin "2") (pinfunction "VLDO6_2") (pintype "passive"))
    )
    (net (code "36") (name "VCC_1V8") (class "Default")
      (node (ref "C49") (pin "2") (pinfunction "2_2") (pintype "passive"))
      (node (ref "L7") (pin "2") (pinfunction "2_2") (pintype "passive"))
      (node (ref "R32") (pin "2") (pinfunction "2_2") (pintype "passive"))
      (node (ref "R33") (pin "2") (pinfunction "2_2") (pintype "passive"))
      (node (ref "U8") (pin "63") (pinfunction "VFB4_63") (pintype "passive"))
    )
    (net (code "37") (name "VCC_3V0") (class "Default")
      (node (ref "C65") (pin "2") (pinfunction "2_2") (pintype "passive"))
      (node (ref "C76") (pin "2") (pinfunction "2_2") (pintype "passive"))
      (node (ref "U8") (pin "15") (pinfunction "VLDO8_15") (pintype "passive"))
      (node (ref "U8") (pin "17") (pinfunction "VDDIO_17") (pintype "passive"))
    )
    (net (code "38") (name "VCC_DDR") (class "Default")
      (node (ref "C52") (pin "2") (pinfunction "2_2") (pintype "passive"))
      (node (ref "C53") (pin "2") (pinfunction "2_2") (pintype "passive"))
      (node (ref "L9") (pin "2") (pinfunction "2_2") (pintype "passive"))
      (node (ref "Q4") (pin "3") (pinfunction "D_3") (pintype "passive"))
      (node (ref "R28") (pin "2") (pinfunction "2_2") (pintype "passive"))
    )
    (net (code "39") (name "VCC_DDRC") (class "Default")
      (node (ref "C84") (pin "2") (pinfunction "2_2") (pintype "passive"))
      (node (ref "Q4") (pin "2") (pinfunction "S_2") (pintype "passive"))
    )
    (net (code "40") (name "VCC_IN_CONN") (class "Default")
      (node (ref "C82") (pin "2") (pinfunction "2_2") (pintype "passive"))
    )
    (net (code "41") (name "VCC_RTC") (class "Default")
      (node (ref "C79") (pin "2") (pinfunction "2_2") (pintype "passive"))
      (node (ref "D1") (pin "K") (pinfunction "K_K") (pintype "passive"))
      (node (ref "U8") (pin "9") (pinfunction "VCCRTC_9") (pintype "passive"))
    )
    (net (code "42") (name "VCC_SDIO") (class "Default")
      (node (ref "C73") (pin "2") (pinfunction "2_2") (pintype "passive"))
      (node (ref "U8") (pin "12") (pinfunction "VLDO4_12") (pintype "passive"))
    )
    (net (code "43") (name "VDC_ONOFF") (class "Default")
      (node (ref "R34") (pin "2") (pinfunction "2_2") (pintype "passive"))
    )
    (net (code "44") (name "VDD_CENTER") (class "Default")
      (node (ref "C50") (pin "2") (pinfunction "2_2") (pintype "passive"))
      (node (ref "C51") (pin "2") (pinfunction "2_2") (pintype "passive"))
      (node (ref "L8") (pin "1") (pinfunction "1_1") (pintype "passive"))
      (node (ref "U8") (pin "39") (pinfunction "VFB1_39") (pintype "passive"))
    )
    (net (code "45") (name "VDD_CPU_L") (class "Default")
      (node (ref "C54") (pin "2") (pinfunction "2_2") (pintype "passive"))
      (node (ref "C55") (pin "2") (pinfunction "2_2") (pintype "passive"))
      (node (ref "L10") (pin "1") (pinfunction "1_1") (pintype "passive"))
      (node (ref "U8") (pin "29") (pinfunction "VFB2_29") (pintype "passive"))
    )
    (net (code "46") (name "unconnected-(U8-CLK32KOUT2-Pad67)") (class "Default")
      (node (ref "U8") (pin "67") (pinfunction "CLK32KOUT2_67") (pintype "passive+no_connect"))
    )
    (net (code "47") (name "unconnected-(U8-DVSOK-Pad54)") (class "Default")
      (node (ref "U8") (pin "54") (pinfunction "DVSOK_54") (pintype "passive+no_connect"))
    )
    (net (code "48") (name "unconnected-(U8-NC1-Pad47)") (class "Default")
      (node (ref "U8") (pin "47") (pinfunction "NC1_47") (pintype "passive+no_connect"))
    )
    (net (code "49") (name "unconnected-(U8-NC2-Pad48)") (class "Default")
      (node (ref "U8") (pin "48") (pinfunction "NC2_48") (pintype "passive+no_connect"))
    )
  )
)
